# TPS56528.net
KiCad netlist of a schematic drawn in EAGLE
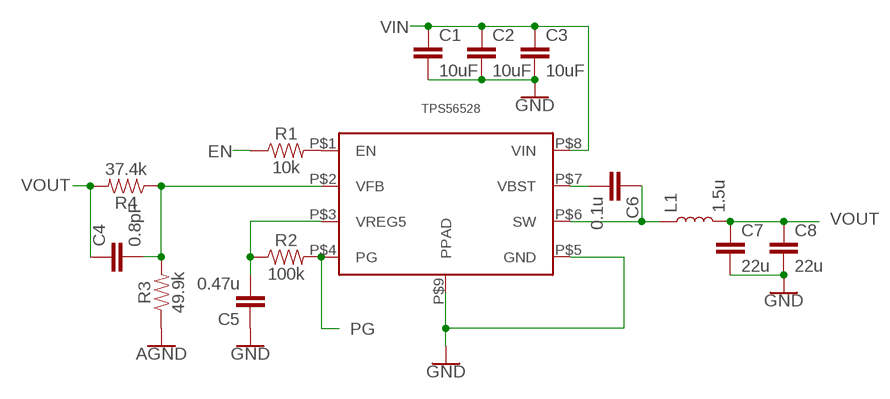
[diagram p0: schematic, sheet 1]

(export (version "E")
  (design (tool "Eeschema 10.0.6"))
  (components
    (comp (ref "C1")
      (value "10uF")
      (footprint "eagle-import:0805")
      (libsource (lib "eagle-import") (part "10UF-0805-10V-10%"))
    )
    (comp (ref "C2")
      (value "10uF")
      (footprint "eagle-import:0805")
      (libsource (lib "eagle-import") (part "10UF-0805-10V-10%"))
    )
    (comp (ref "C3")
      (value "10uF")
      (footprint "eagle-import:0805")
      (libsource (lib "eagle-import") (part "10UF-0805-10V-10%"))
    )
    (comp (ref "C4")
      (value "0.8pF")
      (footprint "eagle-import:0402")
      (libsource (lib "eagle-import") (part "0.8PF-0402-50V-0.1PF"))
    )
    (comp (ref "C5")
      (value "0.47u")
      (footprint "eagle-import:0402")
      (libsource (lib "eagle-import") (part "0.8PF-0402-50V-0.1PF"))
    )
    (comp (ref "C6")
      (value "0.1u")
      (footprint "eagle-import:0402")
      (libsource (lib "eagle-import") (part "0.8PF-0402-50V-0.1PF"))
    )
    (comp (ref "C7")
      (value "22u")
      (footprint "eagle-import:0402")
      (libsource (lib "eagle-import") (part "0.8PF-0402-50V-0.1PF"))
    )
    (comp (ref "C8")
      (value "22u")
      (footprint "eagle-import:0402")
      (libsource (lib "eagle-import") (part "0.8PF-0402-50V-0.1PF"))
    )
    (comp (ref "L1")
      (value "1.5u")
      (footprint "eagle-import:0402")
      (libsource (lib "eagle-import") (part "INDUCTOR-0402-3.9NH"))
    )
    (comp (ref "R1")
      (value "10k")
      (footprint "eagle-import:0402")
      (libsource (lib "eagle-import") (part "22OHM-0402-1/10W-1%"))
    )
    (comp (ref "R2")
      (value "100k")
      (footprint "eagle-import:0402")
      (libsource (lib "eagle-import") (part "22OHM-0402-1/10W-1%"))
    )
    (comp (ref "R3")
      (value "49.9k")
      (footprint "eagle-import:0402")
      (libsource (lib "eagle-import") (part "22OHM-0402-1/10W-1%"))
    )
    (comp (ref "R4")
      (value "37.4k")
      (footprint "eagle-import:0402")
      (libsource (lib "eagle-import") (part "22OHM-0402-1/10W-1%"))
    )
    (comp (ref "U$1")
      (value "TPS56528")
      (footprint "eagle-import:DDA(8-POWERSOIC)")
      (libsource (lib "eagle-import") (part "TPS56528"))
    )
  )
  (nets
    (net (code "1") (name "/EN") (class "Default")
      (node (ref "R1") (pin "1") (pinfunction "1_1") (pintype "passive"))
    )
    (net (code "2") (name "/PG") (class "Default")
      (node (ref "R2") (pin "2") (pinfunction "2_2") (pintype "passive"))
      (node (ref "U$1") (pin "P$4") (pinfunction "PG_P$4") (pintype "bidirectional"))
    )
    (net (code "3") (name "/VIN") (class "Default")
      (node (ref "C1") (pin "1") (pinfunction "1_1") (pintype "passive"))
      (node (ref "C2") (pin "1") (pinfunction "1_1") (pintype "passive"))
      (node (ref "C3") (pin "1") (pinfunction "1_1") (pintype "passive"))
      (node (ref "U$1") (pin "P$8") (pinfunction "VIN_P$8") (pintype "bidirectional"))
    )
    (net (code "4") (name "/VOUT") (class "Default")
      (node (ref "C4") (pin "1") (pinfunction "1_1") (pintype "passive"))
      (node (ref "C7") (pin "1") (pinfunction "1_1") (pintype "passive"))
      (node (ref "C8") (pin "1") (pinfunction "1_1") (pintype "passive"))
      (node (ref "L1") (pin "2") (pinfunction "2_2") (pintype "passive"))
      (node (ref "R4") (pin "2") (pinfunction "2_2") (pintype "passive"))
    )
    (net (code "5") (name "AGND") (class "Default")
      (node (ref "R3") (pin "1") (pinfunction "1_1") (pintype "passive"))
    )
    (net (code "6") (name "GND") (class "Default")
      (node (ref "C1") (pin "2") (pinfunction "2_2") (pintype "passive"))
      (node (ref "C2") (pin "2") (pinfunction "2_2") (pintype "passive"))
      (node (ref "C3") (pin "2") (pinfunction "2_2") (pintype "passive"))
      (node (ref "C5") (pin "1") (pinfunction "1_1") (pintype "passive"))
      (node (ref "C7") (pin "2") (pinfunction "2_2") (pintype "passive"))
      (node (ref "C8") (pin "2") (pinfunction "2_2") (pintype "passive"))
      (node (ref "U$1") (pin "P$5") (pinfunction "GND_P$5") (pintype "bidirectional"))
      (node (ref "U$1") (pin "P$9") (pinfunction "PPAD_P$9") (pintype "bidirectional"))
    )
    (net (code "7") (name "Net-(U$1-EN)") (class "Default")
      (node (ref "R1") (pin "2") (pinfunction "2_2") (pintype "passive"))
      (node (ref "U$1") (pin "P$1") (pinfunction "EN_P$1") (pintype "bidirectional"))
    )
    (net (code "8") (name "Net-(U$1-SW)") (class "Default")
      (node (ref "C6") (pin "1") (pinfunction "1_1") (pintype "passive"))
      (node (ref "L1") (pin "1") (pinfunction "1_1") (pintype "passive"))
      (node (ref "U$1") (pin "P$6") (pinfunction "SW_P$6") (pintype "bidirectional"))
    )
    (net (code "9") (name "Net-(U$1-VBST)") (class "Default")
      (node (ref "C6") (pin "2") (pinfunction "2_2") (pintype "passive"))
      (node (ref "U$1") (pin "P$7") (pinfunction "VBST_P$7") (pintype "bidirectional"))
    )
    (net (code "10") (name "Net-(U$1-VFB)") (class "Default")
      (node (ref "C4") (pin "2") (pinfunction "2_2") (pintype "passive"))
      (node (ref "R3") (pin "2") (pinfunction "2_2") (pintype "passive"))
      (node (ref "R4") (pin "1") (pinfunction "1_1") (pintype "passive"))
      (node (ref "U$1") (pin "P$2") (pinfunction "VFB_P$2") (pintype "bidirectional"))
    )
    (net (code "11") (name "Net-(U$1-VREG5)") (class "Default")
      (node (ref "C5") (pin "2") (pinfunction "2_2") (pintype "passive"))
      (node (ref "R2") (pin "1") (pinfunction "1_1") (pintype "passive"))
      (node (ref "U$1") (pin "P$3") (pinfunction "VREG5_P$3") (pintype "bidirectional"))
    )
  )
)
